# PDOC.net
KiCad netlist of a schematic drawn in Altium Designer
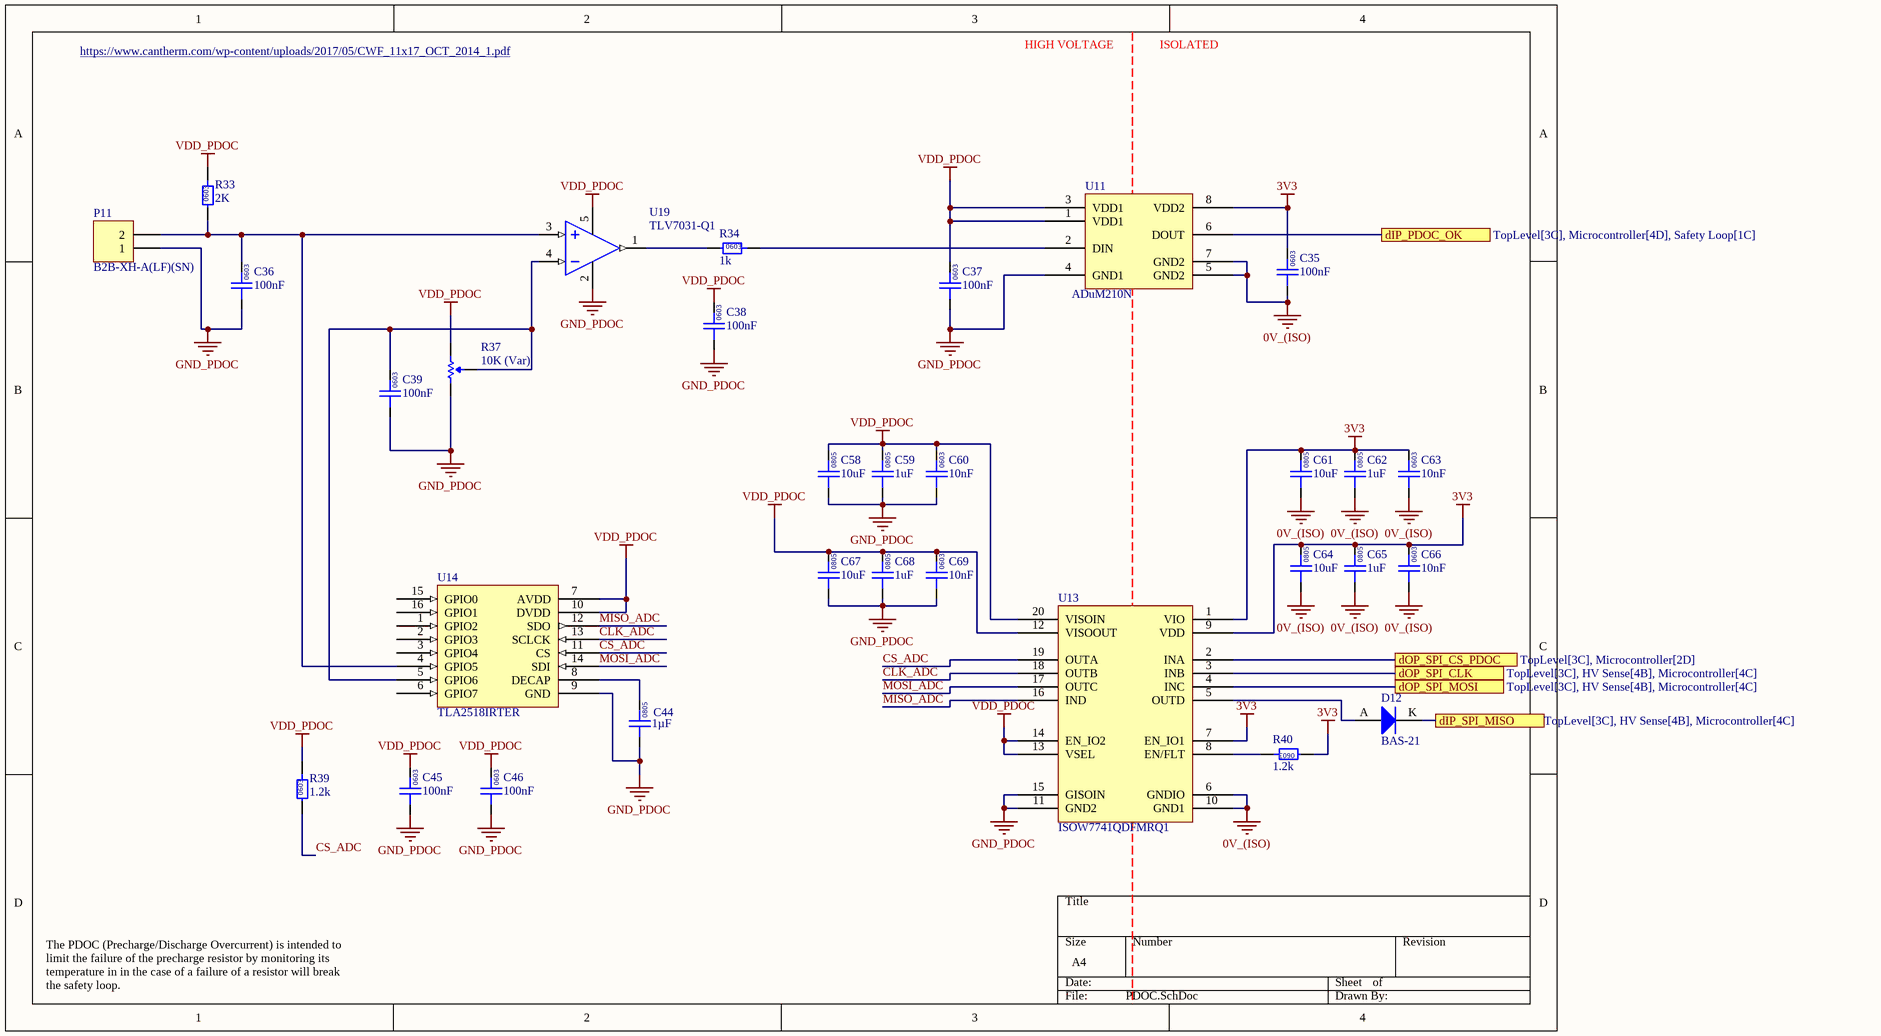
[diagram p0: PDOC.SchDoc]

(export (version "E")
  (design (tool "Eeschema 10.0.6"))
  (components
    (comp (ref "C35")
      (value "100nF")
      (footprint "0603")
      (fields
        (field (name "PART NUMBER") "GCM188L81H104KA57D")
        (field (name "MANUFACTURER") "muRata")
        (field (name "TOLERANCE") "±10%")
      )
      (libsource (lib "ts_standard_library") (part "Capacitor 0603"))
    )
    (comp (ref "C36")
      (value "100nF")
      (footprint "0603")
      (fields
        (field (name "PART NUMBER") "GCM188L81H104KA57D")
        (field (name "MANUFACTURER") "muRata")
        (field (name "TOLERANCE") "±10%")
      )
      (libsource (lib "ts_standard_library") (part "Capacitor 0603"))
    )
    (comp (ref "C37")
      (value "100nF")
      (footprint "0603")
      (fields
        (field (name "PART NUMBER") "GCM188L81H104KA57D")
        (field (name "MANUFACTURER") "muRata")
        (field (name "TOLERANCE") "±10%")
      )
      (libsource (lib "ts_standard_library") (part "Capacitor 0603"))
    )
    (comp (ref "C38")
      (value "100nF")
      (footprint "0603")
      (fields
        (field (name "PART NUMBER") "GCM188L81H104KA57D")
        (field (name "MANUFACTURER") "muRata")
        (field (name "TOLERANCE") "±10%")
      )
      (libsource (lib "ts_standard_library") (part "Capacitor 0603"))
    )
    (comp (ref "C39")
      (value "100nF")
      (footprint "0603")
      (fields
        (field (name "PART NUMBER") "GCM188L81H104KA57D")
        (field (name "MANUFACTURER") "muRata")
        (field (name "TOLERANCE") "±10%")
      )
      (libsource (lib "ts_standard_library") (part "Capacitor 0603"))
    )
    (comp (ref "C44")
      (value "1µF")
      (footprint "0805")
      (fields
        (field (name "PART NUMBER") "GCM21BR71H105KA03L")
        (field (name "MANUFACTURER") "muRata")
        (field (name "TOLERANCE") "±10%")
      )
      (libsource (lib "ts_standard_library") (part "Capacitor 0805"))
    )
    (comp (ref "C45")
      (value "100nF")
      (footprint "0603")
      (fields
        (field (name "PART NUMBER") "GCM188L81H104KA57D")
        (field (name "MANUFACTURER") "muRata")
        (field (name "TOLERANCE") "±10%")
      )
      (libsource (lib "ts_standard_library") (part "Capacitor 0603"))
    )
    (comp (ref "C46")
      (value "100nF")
      (footprint "0603")
      (fields
        (field (name "PART NUMBER") "GCM188L81H104KA57D")
        (field (name "MANUFACTURER") "muRata")
        (field (name "TOLERANCE") "±10%")
      )
      (libsource (lib "ts_standard_library") (part "Capacitor 0603"))
    )
    (comp (ref "C58")
      (value "10uF")
      (footprint "GCM21BR71H105KA03L-Footprint-1")
      (fields (field (name "PART NUMBER") "GRM21BR6YA106KE43L") (field (name "TOLERANCE") "10%"))
      (libsource (lib "Team Swinburne") (part "Component_1"))
    )
    (comp (ref "C59")
      (value "1uF")
      (footprint "GCM21BR71H105KA03L-Footprint-1")
      (fields (field (name "TOLERANCE") "10%") (field (name "PART NUMBER") "GCM21BR71H105KA03L"))
      (libsource (lib "Team Swinburne") (part "Component_1"))
    )
    (comp (ref "C60")
      (value "10nF")
      (footprint "0603 Capacitor")
      (fields (field (name "PART NUMBER") "GCM1885C1H103JA16D") (field (name "TOLERANCE") "5%"))
      (libsource (lib "Team Swinburne") (part "10nF"))
    )
    (comp (ref "C61")
      (value "10uF")
      (footprint "GCM21BR71H105KA03L-Footprint-1")
      (fields (field (name "PART NUMBER") "GRM21BR6YA106KE43L") (field (name "TOLERANCE") "10%"))
      (libsource (lib "Team Swinburne") (part "Component_1"))
    )
    (comp (ref "C62")
      (value "1uF")
      (footprint "GCM21BR71H105KA03L-Footprint-1")
      (fields (field (name "TOLERANCE") "10%") (field (name "PART NUMBER") "GCM21BR71H105KA03L"))
      (libsource (lib "Team Swinburne") (part "Component_1"))
    )
    (comp (ref "C63")
      (value "10nF")
      (footprint "0603 Capacitor")
      (fields (field (name "PART NUMBER") "GCM1885C1H103JA16D") (field (name "TOLERANCE") "5%"))
      (libsource (lib "Team Swinburne") (part "10nF"))
    )
    (comp (ref "C64")
      (value "10uF")
      (footprint "GCM21BR71H105KA03L-Footprint-1")
      (fields (field (name "PART NUMBER") "GRM21BR6YA106KE43L") (field (name "TOLERANCE") "10%"))
      (libsource (lib "Team Swinburne") (part "Component_1"))
    )
    (comp (ref "C65")
      (value "1uF")
      (footprint "GCM21BR71H105KA03L-Footprint-1")
      (fields (field (name "TOLERANCE") "10%") (field (name "PART NUMBER") "GCM21BR71H105KA03L"))
      (libsource (lib "Team Swinburne") (part "Component_1"))
    )
    (comp (ref "C66")
      (value "10nF")
      (footprint "0603 Capacitor")
      (fields (field (name "PART NUMBER") "GCM1885C1H103JA16D") (field (name "TOLERANCE") "5%"))
      (libsource (lib "Team Swinburne") (part "10nF"))
    )
    (comp (ref "C67")
      (value "10uF")
      (footprint "GCM21BR71H105KA03L-Footprint-1")
      (fields (field (name "PART NUMBER") "GRM21BR6YA106KE43L") (field (name "TOLERANCE") "10%"))
      (libsource (lib "Team Swinburne") (part "Component_1"))
    )
    (comp (ref "C68")
      (value "1uF")
      (footprint "GCM21BR71H105KA03L-Footprint-1")
      (fields (field (name "TOLERANCE") "10%") (field (name "PART NUMBER") "GCM21BR71H105KA03L"))
      (libsource (lib "Team Swinburne") (part "Component_1"))
    )
    (comp (ref "C69")
      (value "10nF")
      (footprint "0603 Capacitor")
      (fields (field (name "PART NUMBER") "GCM1885C1H103JA16D") (field (name "TOLERANCE") "5%"))
      (libsource (lib "Team Swinburne") (part "10nF"))
    )
    (comp (ref "D12")
      (value "BAS-21")
      (footprint "NEXPERIA_SOT23")
      (fields (field (name "MANUFACTURER") "Nexperia USA Inc."))
      (libsource (lib "ts_standard_library") (part "Diode"))
    )
    (comp (ref "P11")
      (value "B2B-XH-A(LF)(SN)")
      (footprint "XH 2 PIN VERT")
      (fields (field (name "DIGIKEY PART NUMBER") "455-2247-ND") (field (name "CONTACT") "Tin"))
      (libsource (lib "ts_standard_connectors") (part "Header 1x2"))
    )
    (comp (ref "R33")
      (value "2K")
      (footprint "0603")
      (fields
        (field (name "PART NUMBER") "RC0603FR-072KL")
        (field (name "MANUFACTURER") "YAGEO")
        (field (name "TOLERANCE") "0.01")
      )
      (libsource (lib "ts_standard_library") (part "Resistor 0603"))
    )
    (comp (ref "R34")
      (value "1k")
      (footprint "0603")
      (fields
        (field (name "PART NUMBER") "RC0603FR-071KL")
        (field (name "MANUFACTURER") "YAGEO")
        (field (name "TOLERANCE") "0.01")
      )
      (libsource (lib "ts_standard_library") (part "Resistor 0603"))
    )
    (comp (ref "R37")
      (value "10K (Var)")
      (footprint "B 3296")
      (fields
        (field (name "PART NUMBER") "3296W-1-103LF")
        (field (name "MANUFACTURER") "Bournes Inc")
        (field (name "TOLERANCE") "0.1")
      )
      (libsource (lib "ts_standard_library") (part "Resistor (Potentiometer)"))
    )
    (comp (ref "R39")
      (value "1.2k")
      (footprint "0603")
      (fields
        (field (name "PART NUMBER") "RC0603JR-071K2L")
        (field (name "MANUFACTURER") "YAGEO")
        (field (name "TOLERANCE") "0.01")
      )
      (libsource (lib "ts_standard_library") (part "Resistor 0603"))
    )
    (comp (ref "R40")
      (value "1.2k")
      (footprint "0603")
      (fields
        (field (name "PART NUMBER") "RC0603JR-071K2L")
        (field (name "MANUFACTURER") "YAGEO")
        (field (name "TOLERANCE") "0.01")
      )
      (libsource (lib "ts_standard_library") (part "Resistor 0603"))
    )
    (comp (ref "U11")
      (value "ADuM210N")
      (footprint "SOIC-8W")
      (description "DIGITAL ISOLATOR, SINGLE CHANNEL")
      (libsource (lib "Team Swinburne") (part "ADuM210N"))
    )
    (comp (ref "U13")
      (value "ISOW7741QDFMRQ1")
      (footprint "TI-SOIC-20")
      (libsource (lib "Team Swinburne") (part "ISOW7741QDFMRQ1"))
    )
    (comp (ref "U14")
      (value "TLA2518IRTER")
      (footprint "QFN50P300X300X80_HS-17N")
      (description "8-Channel Single ADC SAR 1Msps 12-bit Serial 16-Pin WQFN EP T/R")
      (libsource (lib "Team Swinburne") (part "TLA518IRTER"))
    )
    (comp (ref "U19")
      (value "TLV7031-Q1")
      (footprint "TI SOT-23-5")
      (fields
        (field (name "MANUFACTURER") "Texas Instruments")
        (field (name "DIGIKEY PART NUMBER") "296-TLV7031QDBVRQ1CT-ND")
      )
      (libsource (lib "ts_standard_library") (part "TLV7031-Q1"))
    )
  )
  (nets
    (net (code "1") (name "/CLK_ADC") (class "Default")
      (node (ref "U13") (pin "18") (pinfunction "OUTB_18") (pintype "passive"))
      (node (ref "U14") (pin "13") (pinfunction "SCLCK_13") (pintype "input"))
    )
    (net (code "2") (name "/CS_ADC") (class "Default")
      (node (ref "R39") (pin "1") (pinfunction "1_1") (pintype "passive"))
      (node (ref "U13") (pin "19") (pinfunction "OUTA_19") (pintype "passive"))
      (node (ref "U14") (pin "11") (pinfunction "CS_11") (pintype "input"))
    )
    (net (code "3") (name "/MISO_ADC") (class "Default")
      (node (ref "U13") (pin "16") (pinfunction "IND_16") (pintype "passive"))
      (node (ref "U14") (pin "12") (pinfunction "SDO_12") (pintype "output"))
    )
    (net (code "4") (name "/MOSI_ADC") (class "Default")
      (node (ref "U13") (pin "17") (pinfunction "OUTC_17") (pintype "passive"))
      (node (ref "U14") (pin "14") (pinfunction "SDI_14") (pintype "input"))
    )
    (net (code "5") (name "/dIP_PDOC_OK") (class "Default")
      (node (ref "U11") (pin "6") (pinfunction "DOUT_6") (pintype "passive"))
    )
    (net (code "6") (name "/dIP_SPI_MISO") (class "Default")
      (node (ref "D12") (pin "K") (pinfunction "K_K") (pintype "passive"))
    )
    (net (code "7") (name "/dOP_SPI_CLK") (class "Default")
      (node (ref "U13") (pin "3") (pinfunction "INB_3") (pintype "passive"))
    )
    (net (code "8") (name "/dOP_SPI_CS_PDOC") (class "Default")
      (node (ref "U13") (pin "2") (pinfunction "INA_2") (pintype "passive"))
    )
    (net (code "9") (name "/dOP_SPI_MOSI") (class "Default")
      (node (ref "U13") (pin "4") (pinfunction "INC_4") (pintype "passive"))
    )
    (net (code "10") (name "0V_(ISO)") (class "Default")
      (node (ref "C35") (pin "1") (pinfunction "1_1") (pintype "passive"))
      (node (ref "C61") (pin "1") (pinfunction "1_1") (pintype "passive"))
      (node (ref "C62") (pin "1") (pinfunction "1_1") (pintype "passive"))
      (node (ref "C63") (pin "1") (pinfunction "1_1") (pintype "passive"))
      (node (ref "C64") (pin "1") (pinfunction "1_1") (pintype "passive"))
      (node (ref "C65") (pin "1") (pinfunction "1_1") (pintype "passive"))
      (node (ref "C66") (pin "1") (pinfunction "1_1") (pintype "passive"))
      (node (ref "U11") (pin "5") (pinfunction "GND2_5") (pintype "passive"))
      (node (ref "U11") (pin "7") (pinfunction "GND2_7") (pintype "passive"))
      (node (ref "U13") (pin "10") (pinfunction "GND1_10") (pintype "passive"))
      (node (ref "U13") (pin "6") (pinfunction "GNDIO_6") (pintype "passive"))
    )
    (net (code "11") (name "3V3") (class "Default")
      (node (ref "C35") (pin "2") (pinfunction "2_2") (pintype "passive"))
      (node (ref "C61") (pin "2") (pinfunction "2_2") (pintype "passive"))
      (node (ref "C62") (pin "2") (pinfunction "2_2") (pintype "passive"))
      (node (ref "C63") (pin "2") (pinfunction "2_2") (pintype "passive"))
      (node (ref "C64") (pin "2") (pinfunction "2_2") (pintype "passive"))
      (node (ref "C65") (pin "2") (pinfunction "2_2") (pintype "passive"))
      (node (ref "C66") (pin "2") (pinfunction "2_2") (pintype "passive"))
      (node (ref "R40") (pin "1") (pinfunction "1_1") (pintype "passive"))
      (node (ref "U11") (pin "8") (pinfunction "VDD2_8") (pintype "passive"))
      (node (ref "U13") (pin "1") (pinfunction "VIO_1") (pintype "passive"))
      (node (ref "U13") (pin "7") (pinfunction "EN_IO1_7") (pintype "passive"))
      (node (ref "U13") (pin "9") (pinfunction "VDD_9") (pintype "passive"))
    )
    (net (code "12") (name "GND_PDOC") (class "Default")
      (node (ref "C36") (pin "1") (pinfunction "1_1") (pintype "passive"))
      (node (ref "C37") (pin "1") (pinfunction "1_1") (pintype "passive"))
      (node (ref "C38") (pin "1") (pinfunction "1_1") (pintype "passive"))
      (node (ref "C39") (pin "1") (pinfunction "1_1") (pintype "passive"))
      (node (ref "C44") (pin "1") (pinfunction "1_1") (pintype "passive"))
      (node (ref "C45") (pin "1") (pinfunction "1_1") (pintype "passive"))
      (node (ref "C46") (pin "1") (pinfunction "1_1") (pintype "passive"))
      (node (ref "C58") (pin "1") (pinfunction "1_1") (pintype "passive"))
      (node (ref "C59") (pin "1") (pinfunction "1_1") (pintype "passive"))
      (node (ref "C60") (pin "1") (pinfunction "1_1") (pintype "passive"))
      (node (ref "C67") (pin "1") (pinfunction "1_1") (pintype "passive"))
      (node (ref "C68") (pin "1") (pinfunction "1_1") (pintype "passive"))
      (node (ref "C69") (pin "1") (pinfunction "1_1") (pintype "passive"))
      (node (ref "P11") (pin "1") (pinfunction "1_1") (pintype "passive"))
      (node (ref "R37") (pin "3") (pinfunction "CW_3") (pintype "passive"))
      (node (ref "U11") (pin "4") (pinfunction "GND1_4") (pintype "passive"))
      (node (ref "U13") (pin "11") (pinfunction "GND2_11") (pintype "passive"))
      (node (ref "U13") (pin "15") (pinfunction "GISOIN_15") (pintype "passive"))
      (node (ref "U14") (pin "9") (pinfunction "GND_9") (pintype "power_in"))
      (node (ref "U19") (pin "2") (pinfunction "V-_2") (pintype "power_in"))
    )
    (net (code "13") (name "Net-(R37-Wiper)") (class "Default")
      (node (ref "C39") (pin "2") (pinfunction "2_2") (pintype "passive"))
      (node (ref "R37") (pin "2") (pinfunction "Wiper_2") (pintype "passive"))
      (node (ref "U14") (pin "5") (pinfunction "GPIO6_5") (pintype "input"))
      (node (ref "U19") (pin "4") (pinfunction "IN-_4") (pintype "input"))
    )
    (net (code "14") (name "Net-(U11-DIN)") (class "Default")
      (node (ref "R34") (pin "2") (pinfunction "2_2") (pintype "passive"))
      (node (ref "U11") (pin "2") (pinfunction "DIN_2") (pintype "passive"))
    )
    (net (code "15") (name "Net-(U13-EN{slash}FLT)") (class "Default")
      (node (ref "R40") (pin "2") (pinfunction "2_2") (pintype "passive"))
      (node (ref "U13") (pin "8") (pinfunction "EN/FLT_8") (pintype "passive"))
    )
    (net (code "16") (name "Net-(U13-OUTD)") (class "Default")
      (node (ref "D12") (pin "A") (pinfunction "A_A") (pintype "passive"))
      (node (ref "U13") (pin "5") (pinfunction "OUTD_5") (pintype "passive"))
    )
    (net (code "17") (name "Net-(U14-DECAP)") (class "Default")
      (node (ref "C44") (pin "2") (pinfunction "2_2") (pintype "passive"))
      (node (ref "U14") (pin "8") (pinfunction "DECAP_8") (pintype "power_in"))
    )
    (net (code "18") (name "Net-(U14-GPIO5)") (class "Default")
      (node (ref "C36") (pin "2") (pinfunction "2_2") (pintype "passive"))
      (node (ref "P11") (pin "2") (pinfunction "2_2") (pintype "passive"))
      (node (ref "R33") (pin "1") (pinfunction "1_1") (pintype "passive"))
      (node (ref "U14") (pin "4") (pinfunction "GPIO5_4") (pintype "input"))
      (node (ref "U19") (pin "3") (pinfunction "IN+_3") (pintype "input"))
    )
    (net (code "19") (name "Net-(U19-OUT)") (class "Default")
      (node (ref "R34") (pin "1") (pinfunction "1_1") (pintype "passive"))
      (node (ref "U19") (pin "1") (pinfunction "OUT_1") (pintype "output"))
    )
    (net (code "20") (name "VDD_PDOC") (class "Default")
      (node (ref "C37") (pin "2") (pinfunction "2_2") (pintype "passive"))
      (node (ref "C38") (pin "2") (pinfunction "2_2") (pintype "passive"))
      (node (ref "C45") (pin "2") (pinfunction "2_2") (pintype "passive"))
      (node (ref "C46") (pin "2") (pinfunction "2_2") (pintype "passive"))
      (node (ref "C58") (pin "2") (pinfunction "2_2") (pintype "passive"))
      (node (ref "C59") (pin "2") (pinfunction "2_2") (pintype "passive"))
      (node (ref "C60") (pin "2") (pinfunction "2_2") (pintype "passive"))
      (node (ref "C67") (pin "2") (pinfunction "2_2") (pintype "passive"))
      (node (ref "C68") (pin "2") (pinfunction "2_2") (pintype "passive"))
      (node (ref "C69") (pin "2") (pinfunction "2_2") (pintype "passive"))
      (node (ref "R33") (pin "2") (pinfunction "2_2") (pintype "passive"))
      (node (ref "R37") (pin "1") (pinfunction "CCW_1") (pintype "passive"))
      (node (ref "R39") (pin "2") (pinfunction "2_2") (pintype "passive"))
      (node (ref "U11") (pin "1") (pinfunction "VDD1_1") (pintype "passive"))
      (node (ref "U11") (pin "3") (pinfunction "VDD1_3") (pintype "passive"))
      (node (ref "U13") (pin "12") (pinfunction "VISOOUT_12") (pintype "passive"))
      (node (ref "U13") (pin "13") (pinfunction "VSEL_13") (pintype "passive"))
      (node (ref "U13") (pin "14") (pinfunction "EN_IO2_14") (pintype "passive"))
      (node (ref "U13") (pin "20") (pinfunction "VISOIN_20") (pintype "passive"))
      (node (ref "U14") (pin "10") (pinfunction "DVDD_10") (pintype "power_in"))
      (node (ref "U14") (pin "7") (pinfunction "AVDD_7") (pintype "power_in"))
      (node (ref "U19") (pin "5") (pinfunction "Vcc_5") (pintype "power_in"))
    )
    (net (code "21") (name "unconnected-(U14-GPIO0-Pad15)") (class "Default")
      (node (ref "U14") (pin "15") (pinfunction "GPIO0_15") (pintype "input"))
    )
    (net (code "22") (name "unconnected-(U14-GPIO1-Pad16)") (class "Default")
      (node (ref "U14") (pin "16") (pinfunction "GPIO1_16") (pintype "input"))
    )
    (net (code "23") (name "unconnected-(U14-GPIO2-Pad1)") (class "Default")
      (node (ref "U14") (pin "1") (pinfunction "GPIO2_1") (pintype "input"))
    )
    (net (code "24") (name "unconnected-(U14-GPIO3-Pad2)") (class "Default")
      (node (ref "U14") (pin "2") (pinfunction "GPIO3_2") (pintype "input"))
    )
    (net (code "25") (name "unconnected-(U14-GPIO4-Pad3)") (class "Default")
      (node (ref "U14") (pin "3") (pinfunction "GPIO4_3") (pintype "input"))
    )
    (net (code "26") (name "unconnected-(U14-GPIO7-Pad6)") (class "Default")
      (node (ref "U14") (pin "6") (pinfunction "GPIO7_6") (pintype "input"))
    )
  )
)
